# as3320-Bandpass.net
KiCad netlist of a schematic drawn in EAGLE
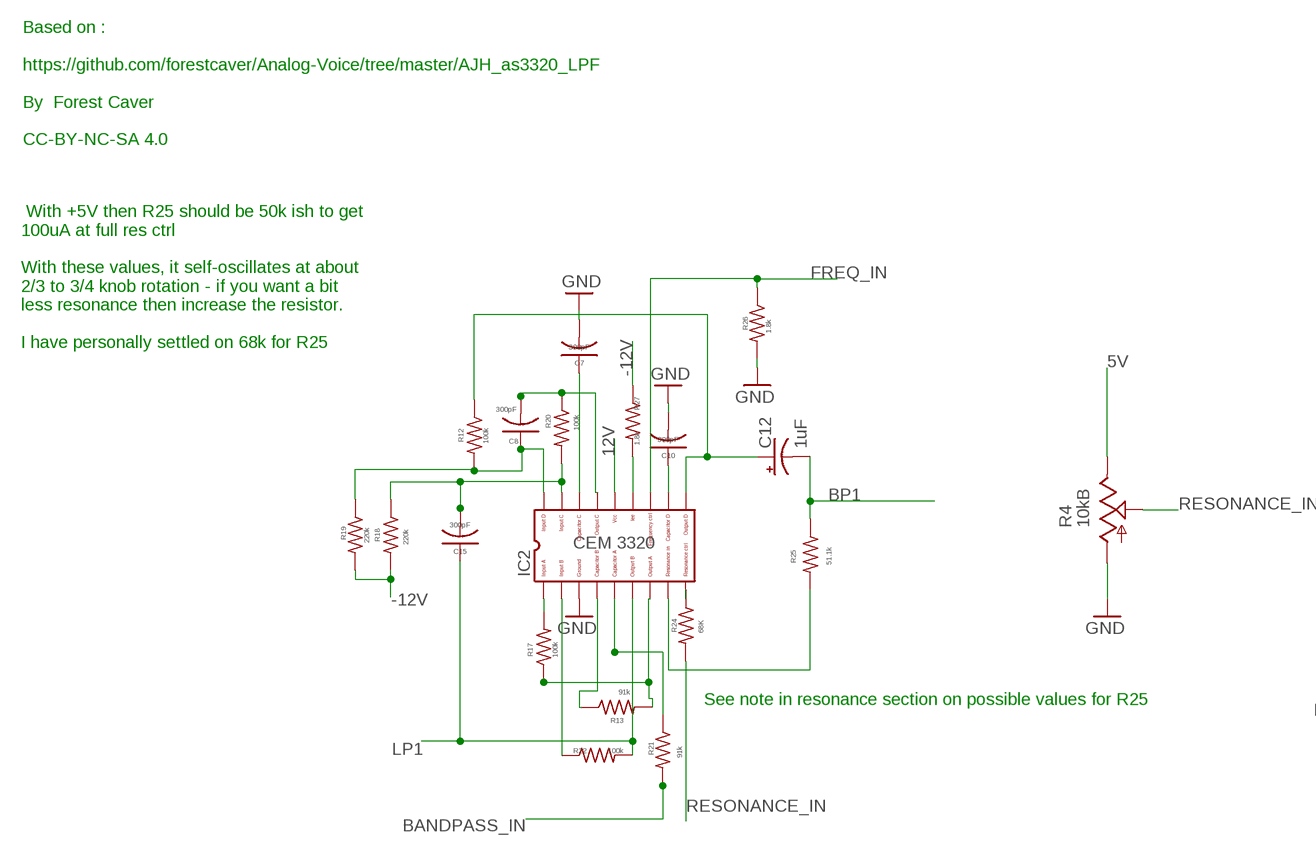
[diagram p0: schematic, sheet 1, part 1 of 2]
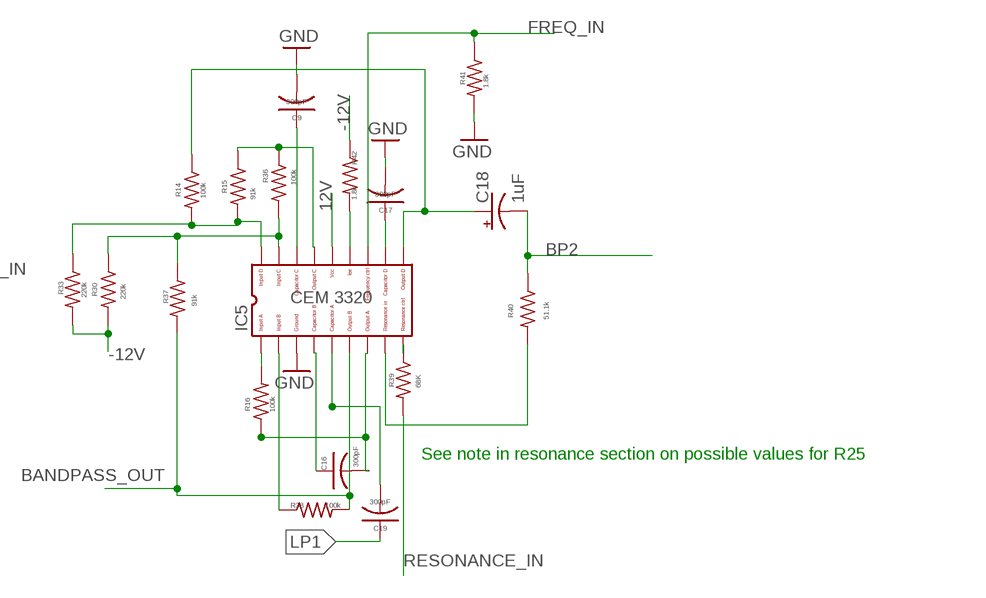
[diagram p1: schematic, sheet 1, part 2 of 2]
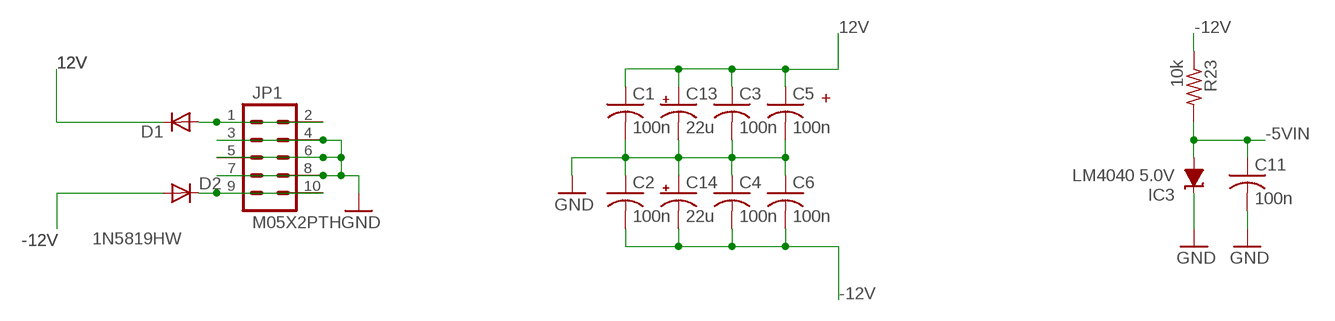
[diagram p2: schematic, sheet 2]
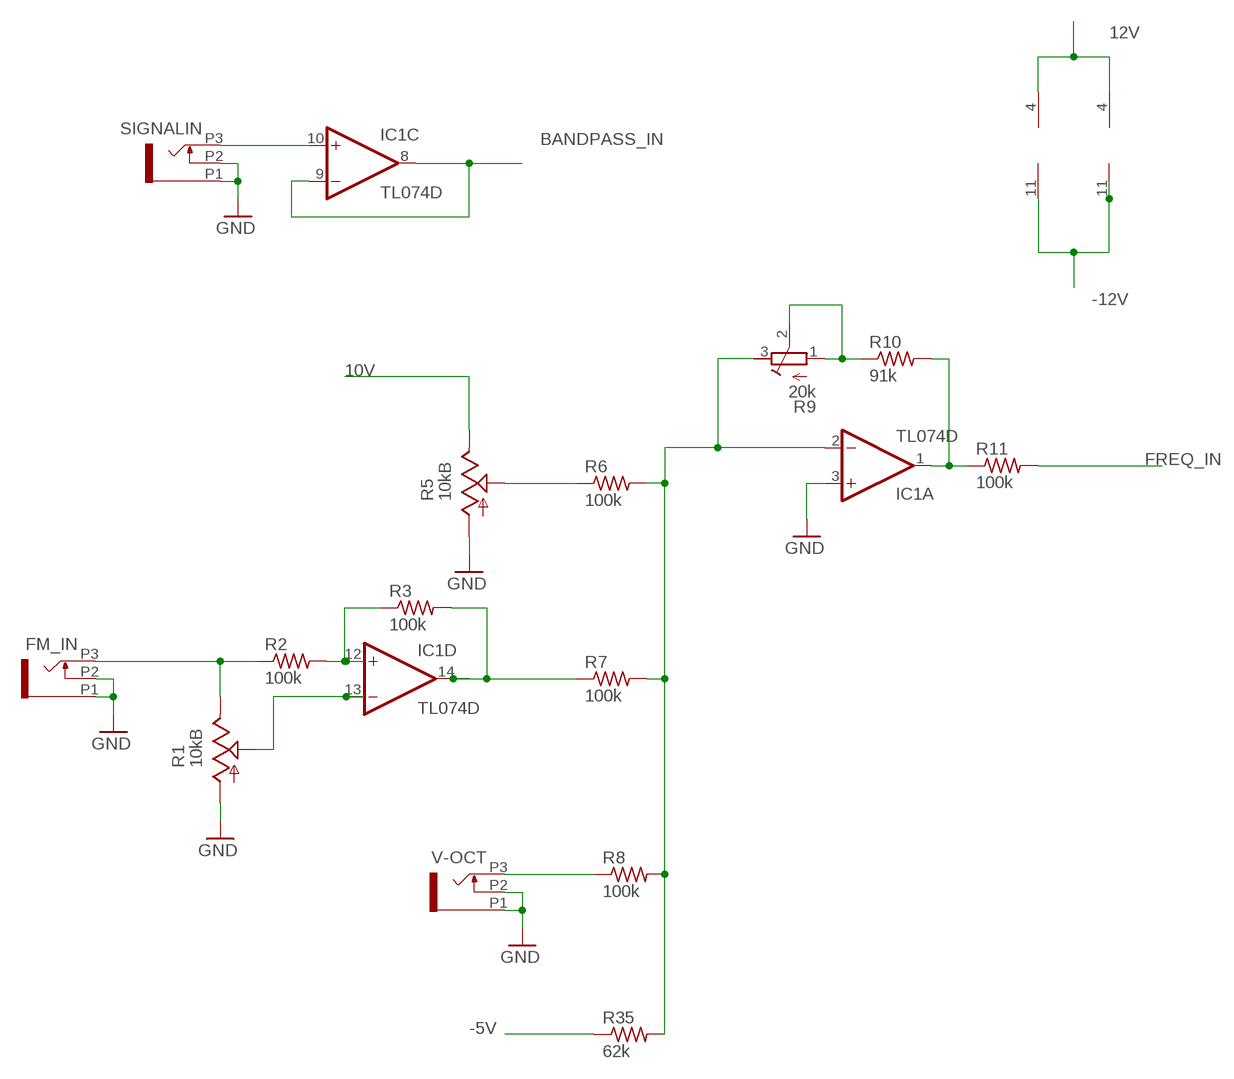
[diagram p3: schematic, sheet 3]
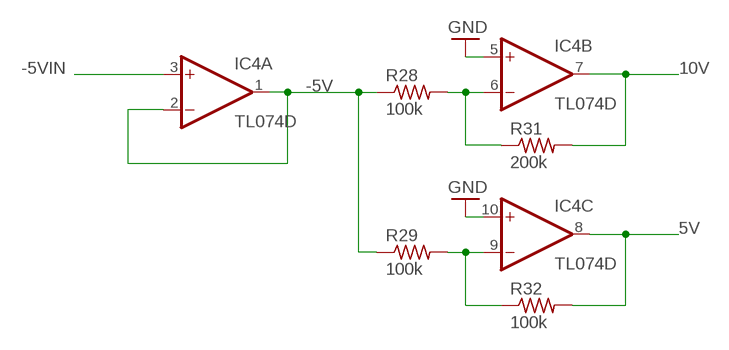
[diagram p4: schematic, sheet 4]
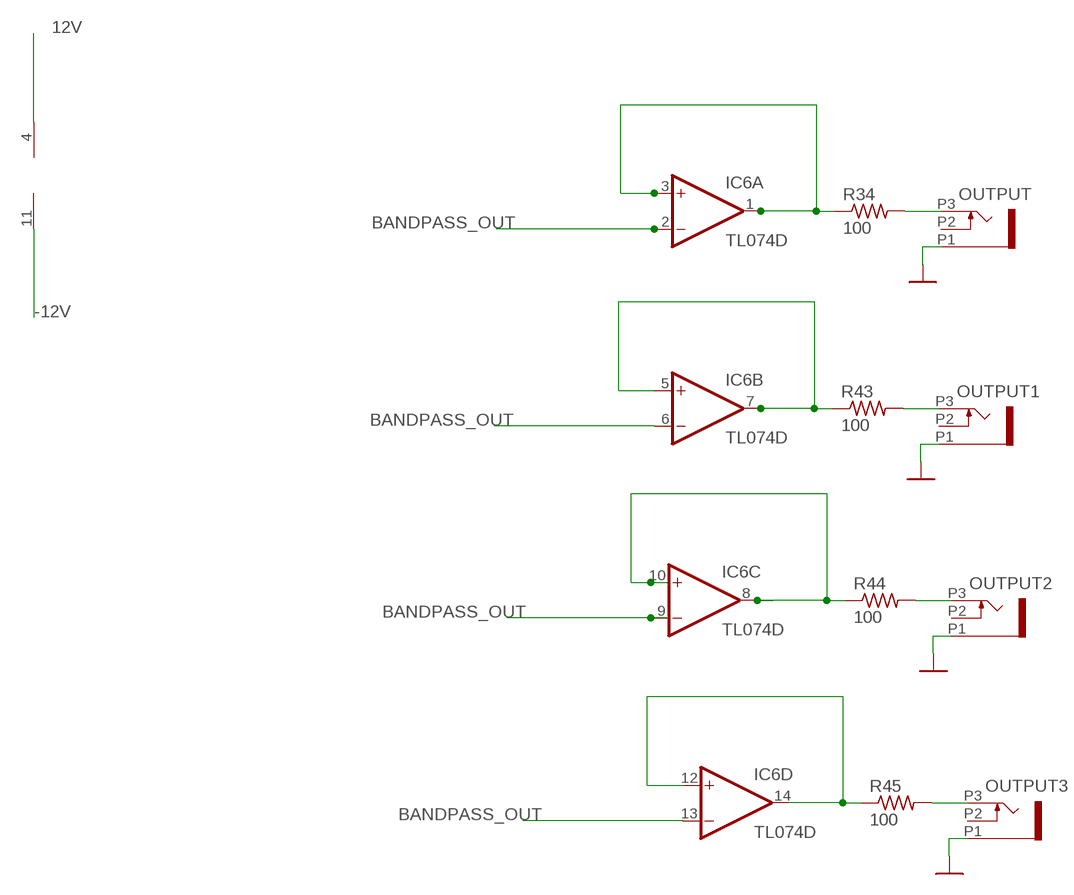
[diagram p5: schematic, sheet 6]

(export (version "E")
  (design (tool "Eeschema 10.0.6"))
  (components
    (comp (ref "C7")
      (value "300pF")
      (footprint "eagle-import:C0603")
      (libsource (lib "eagle-import") (part "rcl_334_C-USC0603"))
    )
    (comp (ref "C8")
      (value "300pF")
      (footprint "eagle-import:C0603")
      (libsource (lib "eagle-import") (part "rcl_334_C-USC0603"))
    )
    (comp (ref "C9")
      (value "300pF")
      (footprint "eagle-import:C0603")
      (libsource (lib "eagle-import") (part "rcl_334_C-USC0603"))
    )
    (comp (ref "C10")
      (value "300pF")
      (footprint "eagle-import:C0603")
      (libsource (lib "eagle-import") (part "rcl_334_C-USC0603"))
    )
    (comp (ref "C12")
      (value "1uF")
      (footprint "eagle-import:PANASONIC_B")
      (libsource (lib "eagle-import") (part "rcl_334_CPOL-USB"))
    )
    (comp (ref "C15")
      (value "300pF")
      (footprint "eagle-import:C0603")
      (libsource (lib "eagle-import") (part "rcl_334_C-USC0603"))
    )
    (comp (ref "C16")
      (value "300pF")
      (footprint "eagle-import:C0603")
      (libsource (lib "eagle-import") (part "rcl_334_C-USC0603"))
    )
    (comp (ref "C17")
      (value "300pF")
      (footprint "eagle-import:C0603")
      (libsource (lib "eagle-import") (part "rcl_334_C-USC0603"))
    )
    (comp (ref "C18")
      (value "1uF")
      (footprint "eagle-import:PANASONIC_B")
      (libsource (lib "eagle-import") (part "rcl_334_CPOL-USB"))
    )
    (comp (ref "C19")
      (value "300pF")
      (footprint "eagle-import:C0603")
      (libsource (lib "eagle-import") (part "rcl_334_C-USC0603"))
    )
    (comp (ref "IC2")
      (value "CEM3320")
      (footprint "eagle-import:DIL18")
      (libsource (lib "eagle-import") (part "CEM3320"))
    )
    (comp (ref "IC5")
      (value "CEM3320")
      (footprint "eagle-import:DIL18")
      (libsource (lib "eagle-import") (part "CEM3320"))
    )
    (comp (ref "R4")
      (value "10kB")
      (footprint "eagle-import:ALPS_POT_VERTICAL")
      (libsource (lib "eagle-import") (part "POT_USVERTICAL"))
    )
    (comp (ref "R12")
      (value "100k")
      (footprint "eagle-import:R0603")
      (libsource (lib "eagle-import") (part "R-US_R0603"))
    )
    (comp (ref "R13")
      (value "91k")
      (footprint "eagle-import:R0603")
      (libsource (lib "eagle-import") (part "R-US_R0603"))
    )
    (comp (ref "R14")
      (value "100k")
      (footprint "eagle-import:R0603")
      (libsource (lib "eagle-import") (part "R-US_R0603"))
    )
    (comp (ref "R15")
      (value "91k")
      (footprint "eagle-import:R0603")
      (libsource (lib "eagle-import") (part "R-US_R0603"))
    )
    (comp (ref "R16")
      (value "100k")
      (footprint "eagle-import:R0603")
      (libsource (lib "eagle-import") (part "R-US_R0603"))
    )
    (comp (ref "R17")
      (value "100k")
      (footprint "eagle-import:R0603")
      (libsource (lib "eagle-import") (part "R-US_R0603"))
    )
    (comp (ref "R18")
      (value "220k")
      (footprint "eagle-import:R0603")
      (libsource (lib "eagle-import") (part "R-US_R0603"))
    )
    (comp (ref "R19")
      (value "220k")
      (footprint "eagle-import:R0603")
      (libsource (lib "eagle-import") (part "R-US_R0603"))
    )
    (comp (ref "R20")
      (value "100k")
      (footprint "eagle-import:R0603")
      (libsource (lib "eagle-import") (part "R-US_R0603"))
    )
    (comp (ref "R21")
      (value "91k")
      (footprint "eagle-import:R0603")
      (libsource (lib "eagle-import") (part "R-US_R0603"))
    )
    (comp (ref "R22")
      (value "100k")
      (footprint "eagle-import:R0603")
      (libsource (lib "eagle-import") (part "R-US_R0603"))
    )
    (comp (ref "R24")
      (value "68K")
      (footprint "eagle-import:R0603")
      (libsource (lib "eagle-import") (part "R-US_R0603"))
    )
    (comp (ref "R25")
      (value "51.1k")
      (footprint "eagle-import:R0603")
      (libsource (lib "eagle-import") (part "R-US_R0603"))
    )
    (comp (ref "R26")
      (value "1.8k")
      (footprint "eagle-import:R0603")
      (libsource (lib "eagle-import") (part "R-US_R0603"))
    )
    (comp (ref "R27")
      (value "1.8k")
      (footprint "eagle-import:R0603")
      (libsource (lib "eagle-import") (part "R-US_R0603"))
    )
    (comp (ref "R30")
      (value "220k")
      (footprint "eagle-import:R0603")
      (libsource (lib "eagle-import") (part "R-US_R0603"))
    )
    (comp (ref "R33")
      (value "220k")
      (footprint "eagle-import:R0603")
      (libsource (lib "eagle-import") (part "R-US_R0603"))
    )
    (comp (ref "R36")
      (value "100k")
      (footprint "eagle-import:R0603")
      (libsource (lib "eagle-import") (part "R-US_R0603"))
    )
    (comp (ref "R37")
      (value "91k")
      (footprint "eagle-import:R0603")
      (libsource (lib "eagle-import") (part "R-US_R0603"))
    )
    (comp (ref "R38")
      (value "100k")
      (footprint "eagle-import:R0603")
      (libsource (lib "eagle-import") (part "R-US_R0603"))
    )
    (comp (ref "R39")
      (value "68K")
      (footprint "eagle-import:R0603")
      (libsource (lib "eagle-import") (part "R-US_R0603"))
    )
    (comp (ref "R40")
      (value "51.1k")
      (footprint "eagle-import:R0603")
      (libsource (lib "eagle-import") (part "R-US_R0603"))
    )
    (comp (ref "R41")
      (value "1.8k")
      (footprint "eagle-import:R0603")
      (libsource (lib "eagle-import") (part "R-US_R0603"))
    )
    (comp (ref "R42")
      (value "1.8k")
      (footprint "eagle-import:R0603")
      (libsource (lib "eagle-import") (part "R-US_R0603"))
    )
    (comp (ref "FM_IN")
      (value "PJ301_THONKICONN6")
      (footprint "eagle-import:WQP_PJ_301M6")
      (libsource (lib "eagle-import") (part "PJ301_THONKICONN6"))
    )
    (comp (ref "IC1")
      (value "TL074D")
      (footprint "eagle-import:SO14")
      (libsource (lib "eagle-import") (part "TL074D"))
    )
    (comp (ref "IC4")
      (value "TL074D")
      (footprint "eagle-import:SO14")
      (libsource (lib "eagle-import") (part "TL074D"))
    )
    (comp (ref "R1")
      (value "10kB")
      (footprint "eagle-import:ALPS_POT_VERTICAL")
      (libsource (lib "eagle-import") (part "POT_USVERTICAL"))
    )
    (comp (ref "R2")
      (value "100k")
      (footprint "eagle-import:R0603")
      (libsource (lib "eagle-import") (part "resistor_R-US_R0603"))
    )
    (comp (ref "R3")
      (value "100k")
      (footprint "eagle-import:R0603")
      (libsource (lib "eagle-import") (part "resistor_R-US_R0603"))
    )
    (comp (ref "R5")
      (value "10kB")
      (footprint "eagle-import:ALPS_POT_VERTICAL")
      (libsource (lib "eagle-import") (part "POT_USVERTICAL"))
    )
    (comp (ref "R6")
      (value "100k")
      (footprint "eagle-import:R0603")
      (libsource (lib "eagle-import") (part "resistor_R-US_R0603"))
    )
    (comp (ref "R7")
      (value "100k")
      (footprint "eagle-import:R0603")
      (libsource (lib "eagle-import") (part "resistor_R-US_R0603"))
    )
    (comp (ref "R8")
      (value "100k")
      (footprint "eagle-import:R0603")
      (libsource (lib "eagle-import") (part "resistor_R-US_R0603"))
    )
    (comp (ref "R9")
      (value "20k")
      (footprint "eagle-import:RTRIM3296X")
      (libsource (lib "eagle-import") (part "R-TRIMM3296X"))
    )
    (comp (ref "R10")
      (value "91k")
      (footprint "eagle-import:R0603")
      (libsource (lib "eagle-import") (part "resistor_R-US_R0603"))
    )
    (comp (ref "R11")
      (value "100k")
      (footprint "eagle-import:R0603")
      (libsource (lib "eagle-import") (part "resistor_R-US_R0603"))
    )
    (comp (ref "R35")
      (value "62k")
      (footprint "eagle-import:R0603")
      (libsource (lib "eagle-import") (part "resistor_R-US_R0603"))
    )
    (comp (ref "SIGNALIN")
      (value "PJ301_THONKICONN6")
      (footprint "eagle-import:WQP_PJ_301M6")
      (libsource (lib "eagle-import") (part "PJ301_THONKICONN6"))
    )
    (comp (ref "V-OCT")
      (value "PJ301_THONKICONN6")
      (footprint "eagle-import:WQP_PJ_301M6")
      (libsource (lib "eagle-import") (part "PJ301_THONKICONN6"))
    )
    (comp (ref "C1")
      (value "100n")
      (footprint "eagle-import:C0603")
      (libsource (lib "eagle-import") (part "C-USC0603"))
    )
    (comp (ref "C2")
      (value "100n")
      (footprint "eagle-import:C0603")
      (libsource (lib "eagle-import") (part "C-USC0603"))
    )
    (comp (ref "C3")
      (value "100n")
      (footprint "eagle-import:C0603")
      (libsource (lib "eagle-import") (part "C-USC0603"))
    )
    (comp (ref "C4")
      (value "100n")
      (footprint "eagle-import:C0603")
      (libsource (lib "eagle-import") (part "C-USC0603"))
    )
    (comp (ref "C5")
      (value "100n")
      (footprint "eagle-import:C0603")
      (libsource (lib "eagle-import") (part "C-USC0603"))
    )
    (comp (ref "C6")
      (value "100n")
      (footprint "eagle-import:C0603")
      (libsource (lib "eagle-import") (part "C-USC0603"))
    )
    (comp (ref "C11")
      (value "100n")
      (footprint "eagle-import:C0603")
      (libsource (lib "eagle-import") (part "C-USC0603"))
    )
    (comp (ref "C13")
      (value "22u")
      (footprint "eagle-import:PANASONIC_B")
      (libsource (lib "eagle-import") (part "CPOL-USB"))
    )
    (comp (ref "C14")
      (value "22u")
      (footprint "eagle-import:PANASONIC_B")
      (libsource (lib "eagle-import") (part "CPOL-USB"))
    )
    (comp (ref "D1")
      (value "1N5819HW")
      (footprint "eagle-import:SOD123")
      (libsource (lib "eagle-import") (part "DIODE-SOD123"))
    )
    (comp (ref "D2")
      (value "1N5819HW")
      (footprint "eagle-import:SOD123")
      (libsource (lib "eagle-import") (part "DIODE-SOD123"))
    )
    (comp (ref "IC3")
      (value "LM4040 5.0V")
      (footprint "eagle-import:DBZ_R-PDSO-G3")
      (libsource (lib "eagle-import") (part "LM4041DBZC12"))
    )
    (comp (ref "JP1")
      (value "M05X2PTH")
      (footprint "eagle-import:AVR_ICSP")
      (libsource (lib "eagle-import") (part "M05X2PTH"))
    )
    (comp (ref "R23")
      (value "10k")
      (footprint "eagle-import:R0603")
      (libsource (lib "eagle-import") (part "resistor_R-US_R0603"))
    )
    (comp (ref "R28")
      (value "100k")
      (footprint "eagle-import:R0603")
      (libsource (lib "eagle-import") (part "resistor_R-US_R0603"))
    )
    (comp (ref "R29")
      (value "100k")
      (footprint "eagle-import:R0603")
      (libsource (lib "eagle-import") (part "resistor_R-US_R0603"))
    )
    (comp (ref "R31")
      (value "200k")
      (footprint "eagle-import:R0603")
      (libsource (lib "eagle-import") (part "resistor_R-US_R0603"))
    )
    (comp (ref "R32")
      (value "100k")
      (footprint "eagle-import:R0603")
      (libsource (lib "eagle-import") (part "resistor_R-US_R0603"))
    )
    (comp (ref "IC6")
      (value "TL074D")
      (footprint "eagle-import:SO14")
      (libsource (lib "eagle-import") (part "TL074D"))
    )
    (comp (ref "OUTPUT")
      (value "PJ301_THONKICONN6")
      (footprint "eagle-import:WQP_PJ_301M6")
      (libsource (lib "eagle-import") (part "PJ301_THONKICONN6"))
    )
    (comp (ref "OUTPUT1")
      (value "PJ301_THONKICONN6")
      (footprint "eagle-import:WQP_PJ_301M6")
      (libsource (lib "eagle-import") (part "PJ301_THONKICONN6"))
    )
    (comp (ref "OUTPUT2")
      (value "PJ301_THONKICONN6")
      (footprint "eagle-import:WQP_PJ_301M6")
      (libsource (lib "eagle-import") (part "PJ301_THONKICONN6"))
    )
    (comp (ref "OUTPUT3")
      (value "PJ301_THONKICONN6")
      (footprint "eagle-import:WQP_PJ_301M6")
      (libsource (lib "eagle-import") (part "PJ301_THONKICONN6"))
    )
    (comp (ref "R34")
      (value "100")
      (footprint "eagle-import:R0603")
      (libsource (lib "eagle-import") (part "resistor_R-US_R0603"))
    )
    (comp (ref "R43")
      (value "100")
      (footprint "eagle-import:R0603")
      (libsource (lib "eagle-import") (part "resistor_R-US_R0603"))
    )
    (comp (ref "R44")
      (value "100")
      (footprint "eagle-import:R0603")
      (libsource (lib "eagle-import") (part "resistor_R-US_R0603"))
    )
    (comp (ref "R45")
      (value "100")
      (footprint "eagle-import:R0603")
      (libsource (lib "eagle-import") (part "resistor_R-US_R0603"))
    )
  )
  (nets
    (net (code "1") (name "-5V") (class "Default")
      (node (ref "IC4") (pin "1") (pinfunction "OUT_1") (pintype "output"))
      (node (ref "IC4") (pin "2") (pinfunction "-IN_2") (pintype "input"))
      (node (ref "R28") (pin "1") (pinfunction "1_1") (pintype "passive"))
      (node (ref "R29") (pin "1") (pinfunction "1_1") (pintype "passive"))
      (node (ref "R35") (pin "1") (pinfunction "1_1") (pintype "passive"))
    )
    (net (code "2") (name "-5VIN") (class "Default")
      (node (ref "C11") (pin "1") (pinfunction "1_1") (pintype "passive"))
      (node (ref "IC3") (pin "2") (pinfunction "A_2") (pintype "passive"))
      (node (ref "IC4") (pin "3") (pinfunction "+IN_3") (pintype "input"))
      (node (ref "R23") (pin "2") (pinfunction "2_2") (pintype "passive"))
    )
    (net (code "3") (name "-12V") (class "Default")
      (node (ref "C14") (pin "-") (pinfunction "-_-") (pintype "passive"))
      (node (ref "C2") (pin "2") (pinfunction "2_2") (pintype "passive"))
      (node (ref "C4") (pin "2") (pinfunction "2_2") (pintype "passive"))
      (node (ref "C6") (pin "2") (pinfunction "2_2") (pintype "passive"))
      (node (ref "D2") (pin "A") (pinfunction "A_A") (pintype "passive"))
      (node (ref "IC1") (pin "11") (pinfunction "V-_11") (pintype "power_in"))
      (node (ref "IC4") (pin "11") (pinfunction "V-_11") (pintype "power_in"))
      (node (ref "IC6") (pin "11") (pinfunction "V-_11") (pintype "power_in"))
      (node (ref "R18") (pin "2") (pinfunction "2_2") (pintype "passive"))
      (node (ref "R19") (pin "2") (pinfunction "2_2") (pintype "passive"))
      (node (ref "R23") (pin "1") (pinfunction "1_1") (pintype "passive"))
      (node (ref "R27") (pin "1") (pinfunction "1_1") (pintype "passive"))
      (node (ref "R30") (pin "2") (pinfunction "2_2") (pintype "passive"))
      (node (ref "R33") (pin "2") (pinfunction "2_2") (pintype "passive"))
      (node (ref "R42") (pin "1") (pinfunction "1_1") (pintype "passive"))
    )
    (net (code "4") (name "5V") (class "Default")
      (node (ref "IC4") (pin "8") (pinfunction "OUT_8") (pintype "output"))
      (node (ref "R32") (pin "2") (pinfunction "2_2") (pintype "passive"))
      (node (ref "R4") (pin "P$1") (pinfunction "E_P$1") (pintype "passive"))
    )
    (net (code "5") (name "10V") (class "Default")
      (node (ref "IC4") (pin "7") (pinfunction "OUT_7") (pintype "output"))
      (node (ref "R31") (pin "2") (pinfunction "2_2") (pintype "passive"))
      (node (ref "R5") (pin "P$1") (pinfunction "E_P$1") (pintype "passive"))
    )
    (net (code "6") (name "12V") (class "Default")
      (node (ref "C1") (pin "1") (pinfunction "1_1") (pintype "passive"))
      (node (ref "C13") (pin "+") (pinfunction "+_+") (pintype "passive"))
      (node (ref "C3") (pin "1") (pinfunction "1_1") (pintype "passive"))
      (node (ref "C5") (pin "1") (pinfunction "1_1") (pintype "passive"))
      (node (ref "D1") (pin "C") (pinfunction "C_C") (pintype "passive"))
      (node (ref "IC1") (pin "4") (pinfunction "V+_4") (pintype "power_in"))
      (node (ref "IC2") (pin "14") (pinfunction "14_14") (pintype "power_in"))
      (node (ref "IC4") (pin "4") (pinfunction "V+_4") (pintype "power_in"))
      (node (ref "IC5") (pin "14") (pinfunction "14_14") (pintype "power_in"))
      (node (ref "IC6") (pin "4") (pinfunction "V+_4") (pintype "power_in"))
    )
    (net (code "7") (name "BANDPASS_IN") (class "Default")
      (node (ref "IC1") (pin "8") (pinfunction "OUT_8") (pintype "output"))
      (node (ref "IC1") (pin "9") (pinfunction "-IN_9") (pintype "input"))
      (node (ref "R21") (pin "2") (pinfunction "2_2") (pintype "passive"))
    )
    (net (code "8") (name "BANDPASS_OUT") (class "Default")
      (node (ref "IC5") (pin "6") (pinfunction "6_6") (pintype "output"))
      (node (ref "IC6") (pin "13") (pinfunction "-IN_13") (pintype "input"))
      (node (ref "IC6") (pin "2") (pinfunction "-IN_2") (pintype "input"))
      (node (ref "IC6") (pin "6") (pinfunction "-IN_6") (pintype "input"))
      (node (ref "IC6") (pin "9") (pinfunction "-IN_9") (pintype "input"))
      (node (ref "R37") (pin "2") (pinfunction "2_2") (pintype "passive"))
      (node (ref "R38") (pin "2") (pinfunction "2_2") (pintype "passive"))
    )
    (net (code "9") (name "BP1") (class "Default")
      (node (ref "C12") (pin "-") (pinfunction "-_-") (pintype "passive"))
      (node (ref "R25") (pin "1") (pinfunction "1_1") (pintype "passive"))
    )
    (net (code "10") (name "BP2") (class "Default")
      (node (ref "C18") (pin "-") (pinfunction "-_-") (pintype "passive"))
      (node (ref "R40") (pin "1") (pinfunction "1_1") (pintype "passive"))
    )
    (net (code "11") (name "FREQ_IN") (class "Default")
      (node (ref "IC2") (pin "12") (pinfunction "12_12") (pintype "bidirectional"))
      (node (ref "IC5") (pin "12") (pinfunction "12_12") (pintype "bidirectional"))
      (node (ref "R11") (pin "2") (pinfunction "2_2") (pintype "passive"))
      (node (ref "R26") (pin "1") (pinfunction "1_1") (pintype "passive"))
      (node (ref "R41") (pin "1") (pinfunction "1_1") (pintype "passive"))
    )
    (net (code "12") (name "GND") (class "Default")
      (node (ref "C1") (pin "2") (pinfunction "2_2") (pintype "passive"))
      (node (ref "C10") (pin "2") (pinfunction "2_2") (pintype "passive"))
      (node (ref "C11") (pin "2") (pinfunction "2_2") (pintype "passive"))
      (node (ref "C13") (pin "-") (pinfunction "-_-") (pintype "passive"))
      (node (ref "C14") (pin "+") (pinfunction "+_+") (pintype "passive"))
      (node (ref "C17") (pin "2") (pinfunction "2_2") (pintype "passive"))
      (node (ref "C2") (pin "1") (pinfunction "1_1") (pintype "passive"))
      (node (ref "C3") (pin "2") (pinfunction "2_2") (pintype "passive"))
      (node (ref "C4") (pin "1") (pinfunction "1_1") (pintype "passive"))
      (node (ref "C5") (pin "2") (pinfunction "2_2") (pintype "passive"))
      (node (ref "C6") (pin "1") (pinfunction "1_1") (pintype "passive"))
      (node (ref "C7") (pin "2") (pinfunction "2_2") (pintype "passive"))
      (node (ref "C9") (pin "2") (pinfunction "2_2") (pintype "passive"))
      (node (ref "FM_IN") (pin "P1") (pinfunction "1_P1") (pintype "passive"))
      (node (ref "FM_IN") (pin "P2") (pinfunction "2_P2") (pintype "passive"))
      (node (ref "IC1") (pin "3") (pinfunction "+IN_3") (pintype "input"))
      (node (ref "IC2") (pin "3") (pinfunction "3_3") (pintype "power_in"))
      (node (ref "IC3") (pin "1") (pinfunction "C_1") (pintype "passive"))
      (node (ref "IC4") (pin "10") (pinfunction "+IN_10") (pintype "input"))
      (node (ref "IC4") (pin "5") (pinfunction "+IN_5") (pintype "input"))
      (node (ref "IC5") (pin "3") (pinfunction "3_3") (pintype "power_in"))
      (node (ref "JP1") (pin "3") (pinfunction "3_3") (pintype "passive"))
      (node (ref "JP1") (pin "4") (pinfunction "4_4") (pintype "passive"))
      (node (ref "JP1") (pin "5") (pinfunction "5_5") (pintype "passive"))
      (node (ref "JP1") (pin "6") (pinfunction "6_6") (pintype "passive"))
      (node (ref "JP1") (pin "7") (pinfunction "7_7") (pintype "passive"))
      (node (ref "JP1") (pin "8") (pinfunction "8_8") (pintype "passive"))
      (node (ref "OUTPUT") (pin "P1") (pinfunction "1_P1") (pintype "passive"))
      (node (ref "OUTPUT1") (pin "P1") (pinfunction "1_P1") (pintype "passive"))
      (node (ref "OUTPUT2") (pin "P1") (pinfunction "1_P1") (pintype "passive"))
      (node (ref "OUTPUT3") (pin "P1") (pinfunction "1_P1") (pintype "passive"))
      (node (ref "R1") (pin "P$3") (pinfunction "A_P$3") (pintype "passive"))
      (node (ref "R26") (pin "2") (pinfunction "2_2") (pintype "passive"))
      (node (ref "R4") (pin "P$3") (pinfunction "A_P$3") (pintype "passive"))
      (node (ref "R41") (pin "2") (pinfunction "2_2") (pintype "passive"))
      (node (ref "R5") (pin "P$3") (pinfunction "A_P$3") (pintype "passive"))
      (node (ref "SIGNALIN") (pin "P1") (pinfunction "1_P1") (pintype "passive"))
      (node (ref "SIGNALIN") (pin "P2") (pinfunction "2_P2") (pintype "passive"))
      (node (ref "V-OCT") (pin "P1") (pinfunction "1_P1") (pintype "passive"))
      (node (ref "V-OCT") (pin "P2") (pinfunction "2_P2") (pintype "passive"))
    )
    (net (code "13") (name "LP1") (class "Default")
      (node (ref "C15") (pin "1") (pinfunction "1_1") (pintype "passive"))
      (node (ref "C19") (pin "1") (pinfunction "1_1") (pintype "passive"))
      (node (ref "IC2") (pin "6") (pinfunction "6_6") (pintype "output"))
      (node (ref "R22") (pin "2") (pinfunction "2_2") (pintype "passive"))
    )
    (net (code "14") (name "Net-(C7-Pad1)") (class "Default")
      (node (ref "C7") (pin "1") (pinfunction "1_1") (pintype "passive"))
      (node (ref "IC2") (pin "16") (pinfunction "16_16") (pintype "bidirectional"))
    )
    (net (code "15") (name "Net-(C8-Pad1)") (class "Default")
      (node (ref "C8") (pin "1") (pinfunction "1_1") (pintype "passive"))
      (node (ref "IC2") (pin "18") (pinfunction "18_18") (pintype "input"))
      (node (ref "R12") (pin "2") (pinfunction "2_2") (pintype "passive"))
      (node (ref "R19") (pin "1") (pinfunction "1_1") (pintype "passive"))
    )
    (net (code "16") (name "Net-(C8-Pad2)") (class "Default")
      (node (ref "C8") (pin "2") (pinfunction "2_2") (pintype "passive"))
      (node (ref "IC2") (pin "15") (pinfunction "15_15") (pintype "output"))
      (node (ref "R20") (pin "1") (pinfunction "1_1") (pintype "passive"))
    )
    (net (code "17") (name "Net-(C9-Pad1)") (class "Default")
      (node (ref "C9") (pin "1") (pinfunction "1_1") (pintype "passive"))
      (node (ref "IC5") (pin "16") (pinfunction "16_16") (pintype "bidirectional"))
    )
    (net (code "18") (name "Net-(C10-Pad1)") (class "Default")
      (node (ref "C10") (pin "1") (pinfunction "1_1") (pintype "passive"))
      (node (ref "IC2") (pin "11") (pinfunction "11_11") (pintype "output"))
    )
    (net (code "19") (name "Net-(C12-Pad+)") (class "Default")
      (node (ref "C12") (pin "+") (pinfunction "+_+") (pintype "passive"))
      (node (ref "IC2") (pin "10") (pinfunction "10_10") (pintype "output"))
      (node (ref "R12") (pin "1") (pinfunction "1_1") (pintype "passive"))
    )
    (net (code "20") (name "Net-(C15-Pad2)") (class "Default")
      (node (ref "C15") (pin "2") (pinfunction "2_2") (pintype "passive"))
      (node (ref "IC2") (pin "17") (pinfunction "17_17") (pintype "input"))
      (node (ref "R18") (pin "1") (pinfunction "1_1") (pintype "passive"))
      (node (ref "R20") (pin "2") (pinfunction "2_2") (pintype "passive"))
    )
    (net (code "21") (name "Net-(C16-Pad1)") (class "Default")
      (node (ref "C16") (pin "1") (pinfunction "1_1") (pintype "passive"))
      (node (ref "IC5") (pin "4") (pinfunction "4_4") (pintype "bidirectional"))
    )
    (net (code "22") (name "Net-(C16-Pad2)") (class "Default")
      (node (ref "C16") (pin "2") (pinfunction "2_2") (pintype "passive"))
      (node (ref "IC5") (pin "7") (pinfunction "7_7") (pintype "output"))
      (node (ref "R16") (pin "1") (pinfunction "1_1") (pintype "passive"))
    )
    (net (code "23") (name "Net-(C17-Pad1)") (class "Default")
      (node (ref "C17") (pin "1") (pinfunction "1_1") (pintype "passive"))
      (node (ref "IC5") (pin "11") (pinfunction "11_11") (pintype "output"))
    )
    (net (code "24") (name "Net-(C18-Pad+)") (class "Default")
      (node (ref "C18") (pin "+") (pinfunction "+_+") (pintype "passive"))
      (node (ref "IC5") (pin "10") (pinfunction "10_10") (pintype "output"))
      (node (ref "R14") (pin "1") (pinfunction "1_1") (pintype "passive"))
    )
    (net (code "25") (name "Net-(C19-Pad2)") (class "Default")
      (node (ref "C19") (pin "2") (pinfunction "2_2") (pintype "passive"))
      (node (ref "IC5") (pin "5") (pinfunction "5_5") (pintype "bidirectional"))
    )
    (net (code "26") (name "Net-(D1-PadA)") (class "Default")
      (node (ref "D1") (pin "A") (pinfunction "A_A") (pintype "passive"))
      (node (ref "JP1") (pin "1") (pinfunction "1_1") (pintype "passive"))
      (node (ref "JP1") (pin "2") (pinfunction "2_2") (pintype "passive"))
    )
    (net (code "27") (name "Net-(D2-PadC)") (class "Default")
      (node (ref "D2") (pin "C") (pinfunction "C_C") (pintype "passive"))
      (node (ref "JP1") (pin "10") (pinfunction "10_10") (pintype "passive"))
      (node (ref "JP1") (pin "9") (pinfunction "9_9") (pintype "passive"))
    )
    (net (code "28") (name "Net-(FM_IN-3)") (class "Default")
      (node (ref "FM_IN") (pin "P3") (pinfunction "3_P3") (pintype "passive"))
      (node (ref "R1") (pin "P$1") (pinfunction "E_P$1") (pintype "passive"))
      (node (ref "R2") (pin "1") (pinfunction "1_1") (pintype "passive"))
    )
    (net (code "29") (name "Net-(IC1A--IN)") (class "Default")
      (node (ref "IC1") (pin "2") (pinfunction "-IN_2") (pintype "input"))
      (node (ref "R35") (pin "2") (pinfunction "2_2") (pintype "passive"))
      (node (ref "R6") (pin "2") (pinfunction "2_2") (pintype "passive"))
      (node (ref "R7") (pin "2") (pinfunction "2_2") (pintype "passive"))
      (node (ref "R8") (pin "2") (pinfunction "2_2") (pintype "passive"))
      (node (ref "R9") (pin "3") (pinfunction "A_3") (pintype "passive"))
    )
    (net (code "30") (name "Net-(IC1A-OUT)") (class "Default")
      (node (ref "IC1") (pin "1") (pinfunction "OUT_1") (pintype "output"))
      (node (ref "R10") (pin "2") (pinfunction "2_2") (pintype "passive"))
      (node (ref "R11") (pin "1") (pinfunction "1_1") (pintype "passive"))
    )
    (net (code "31") (name "Net-(IC1C-+IN)") (class "Default")
      (node (ref "IC1") (pin "10") (pinfunction "+IN_10") (pintype "input"))
      (node (ref "SIGNALIN") (pin "P3") (pinfunction "3_P3") (pintype "passive"))
    )
    (net (code "32") (name "Net-(IC1D-+IN)") (class "Default")
      (node (ref "IC1") (pin "12") (pinfunction "+IN_12") (pintype "input"))
      (node (ref "R2") (pin "2") (pinfunction "2_2") (pintype "passive"))
      (node (ref "R3") (pin "1") (pinfunction "1_1") (pintype "passive"))
    )
    (net (code "33") (name "Net-(IC1D--IN)") (class "Default")
      (node (ref "IC1") (pin "13") (pinfunction "-IN_13") (pintype "input"))
      (node (ref "R1") (pin "P$2") (pinfunction "S_P$2") (pintype "passive"))
    )
    (net (code "34") (name "Net-(IC1D-OUT)") (class "Default")
      (node (ref "IC1") (pin "14") (pinfunction "OUT_14") (pintype "output"))
      (node (ref "R3") (pin "2") (pinfunction "2_2") (pintype "passive"))
      (node (ref "R7") (pin "1") (pinfunction "1_1") (pintype "passive"))
    )
    (net (code "35") (name "Net-(IC2-Pad1)") (class "Default")
      (node (ref "IC2") (pin "1") (pinfunction "1_1") (pintype "input"))
      (node (ref "R17") (pin "2") (pinfunction "2_2") (pintype "passive"))
    )
    (net (code "36") (name "Net-(IC2-Pad2)") (class "Default")
      (node (ref "IC2") (pin "2") (pinfunction "2_2") (pintype "input"))
      (node (ref "R22") (pin "1") (pinfunction "1_1") (pintype "passive"))
    )
    (net (code "37") (name "Net-(IC2-Pad4)") (class "Default")
      (node (ref "IC2") (pin "4") (pinfunction "4_4") (pintype "bidirectional"))
      (node (ref "R13") (pin "1") (pinfunction "1_1") (pintype "passive"))
    )
    (net (code "38") (name "Net-(IC2-Pad5)") (class "Default")
      (node (ref "IC2") (pin "5") (pinfunction "5_5") (pintype "bidirectional"))
      (node (ref "R21") (pin "1") (pinfunction "1_1") (pintype "passive"))
    )
    (net (code "39") (name "Net-(IC2-Pad7)") (class "Default")
      (node (ref "IC2") (pin "7") (pinfunction "7_7") (pintype "output"))
      (node (ref "R13") (pin "2") (pinfunction "2_2") (pintype "passive"))
      (node (ref "R17") (pin "1") (pinfunction "1_1") (pintype "passive"))
    )
    (net (code "40") (name "Net-(IC2-Pad8)") (class "Default")
      (node (ref "IC2") (pin "8") (pinfunction "8_8") (pintype "input"))
      (node (ref "R25") (pin "2") (pinfunction "2_2") (pintype "passive"))
    )
    (net (code "41") (name "Net-(IC2-Pad9)") (class "Default")
      (node (ref "IC2") (pin "9") (pinfunction "9_9") (pintype "input"))
      (node (ref "R24") (pin "1") (pinfunction "1_1") (pintype "passive"))
    )
    (net (code "42") (name "Net-(IC2-Pad13)") (class "Default")
      (node (ref "IC2") (pin "13") (pinfunction "13_13") (pintype "power_in"))
      (node (ref "R27") (pin "2") (pinfunction "2_2") (pintype "passive"))
    )
    (net (code "43") (name "Net-(IC4B--IN)") (class "Default")
      (node (ref "IC4") (pin "6") (pinfunction "-IN_6") (pintype "input"))
      (node (ref "R28") (pin "2") (pinfunction "2_2") (pintype "passive"))
      (node (ref "R31") (pin "1") (pinfunction "1_1") (pintype "passive"))
    )
    (net (code "44") (name "Net-(IC4C--IN)") (class "Default")
      (node (ref "IC4") (pin "9") (pinfunction "-IN_9") (pintype "input"))
      (node (ref "R29") (pin "2") (pinfunction "2_2") (pintype "passive"))
      (node (ref "R32") (pin "1") (pinfunction "1_1") (pintype "passive"))
    )
    (net (code "45") (name "Net-(IC5-Pad1)") (class "Default")
      (node (ref "IC5") (pin "1") (pinfunction "1_1") (pintype "input"))
      (node (ref "R16") (pin "2") (pinfunction "2_2") (pintype "passive"))
    )
    (net (code "46") (name "Net-(IC5-Pad2)") (class "Default")
      (node (ref "IC5") (pin "2") (pinfunction "2_2") (pintype "input"))
      (node (ref "R38") (pin "1") (pinfunction "1_1") (pintype "passive"))
    )
    (net (code "47") (name "Net-(IC5-Pad8)") (class "Default")
      (node (ref "IC5") (pin "8") (pinfunction "8_8") (pintype "input"))
      (node (ref "R40") (pin "2") (pinfunction "2_2") (pintype "passive"))
    )
    (net (code "48") (name "Net-(IC5-Pad9)") (class "Default")
      (node (ref "IC5") (pin "9") (pinfunction "9_9") (pintype "input"))
      (node (ref "R39") (pin "1") (pinfunction "1_1") (pintype "passive"))
    )
    (net (code "49") (name "Net-(IC5-Pad13)") (class "Default")
      (node (ref "IC5") (pin "13") (pinfunction "13_13") (pintype "power_in"))
      (node (ref "R42") (pin "2") (pinfunction "2_2") (pintype "passive"))
    )
    (net (code "50") (name "Net-(IC5-Pad15)") (class "Default")
      (node (ref "IC5") (pin "15") (pinfunction "15_15") (pintype "output"))
      (node (ref "R15") (pin "1") (pinfunction "1_1") (pintype "passive"))
      (node (ref "R36") (pin "1") (pinfunction "1_1") (pintype "passive"))
    )
    (net (code "51") (name "Net-(IC5-Pad17)") (class "Default")
      (node (ref "IC5") (pin "17") (pinfunction "17_17") (pintype "input"))
      (node (ref "R30") (pin "1") (pinfunction "1_1") (pintype "passive"))
      (node (ref "R36") (pin "2") (pinfunction "2_2") (pintype "passive"))
      (node (ref "R37") (pin "1") (pinfunction "1_1") (pintype "passive"))
    )
    (net (code "52") (name "Net-(IC5-Pad18)") (class "Default")
      (node (ref "IC5") (pin "18") (pinfunction "18_18") (pintype "input"))
      (node (ref "R14") (pin "2") (pinfunction "2_2") (pintype "passive"))
      (node (ref "R15") (pin "2") (pinfunction "2_2") (pintype "passive"))
      (node (ref "R33") (pin "1") (pinfunction "1_1") (pintype "passive"))
    )
    (net (code "53") (name "Net-(IC6A-+IN)") (class "Default")
      (node (ref "IC6") (pin "1") (pinfunction "OUT_1") (pintype "output"))
      (node (ref "IC6") (pin "3") (pinfunction "+IN_3") (pintype "input"))
      (node (ref "R34") (pin "1") (pinfunction "1_1") (pintype "passive"))
    )
    (net (code "54") (name "Net-(IC6B-+IN)") (class "Default")
      (node (ref "IC6") (pin "5") (pinfunction "+IN_5") (pintype "input"))
      (node (ref "IC6") (pin "7") (pinfunction "OUT_7") (pintype "output"))
      (node (ref "R43") (pin "1") (pinfunction "1_1") (pintype "passive"))
    )
    (net (code "55") (name "Net-(IC6C-+IN)") (class "Default")
      (node (ref "IC6") (pin "10") (pinfunction "+IN_10") (pintype "input"))
      (node (ref "IC6") (pin "8") (pinfunction "OUT_8") (pintype "output"))
      (node (ref "R44") (pin "1") (pinfunction "1_1") (pintype "passive"))
    )
    (net (code "56") (name "Net-(IC6D-+IN)") (class "Default")
      (node (ref "IC6") (pin "12") (pinfunction "+IN_12") (pintype "input"))
      (node (ref "IC6") (pin "14") (pinfunction "OUT_14") (pintype "output"))
      (node (ref "R45") (pin "1") (pinfunction "1_1") (pintype "passive"))
    )
    (net (code "57") (name "Net-(OUTPUT-3)") (class "Default")
      (node (ref "OUTPUT") (pin "P3") (pinfunction "3_P3") (pintype "passive"))
      (node (ref "R34") (pin "2") (pinfunction "2_2") (pintype "passive"))
    )
    (net (code "58") (name "Net-(OUTPUT1-3)") (class "Default")
      (node (ref "OUTPUT1") (pin "P3") (pinfunction "3_P3") (pintype "passive"))
      (node (ref "R43") (pin "2") (pinfunction "2_2") (pintype "passive"))
    )
    (net (code "59") (name "Net-(OUTPUT2-3)") (class "Default")
      (node (ref "OUTPUT2") (pin "P3") (pinfunction "3_P3") (pintype "passive"))
      (node (ref "R44") (pin "2") (pinfunction "2_2") (pintype "passive"))
    )
    (net (code "60") (name "Net-(OUTPUT3-3)") (class "Default")
      (node (ref "OUTPUT3") (pin "P3") (pinfunction "3_P3") (pintype "passive"))
      (node (ref "R45") (pin "2") (pinfunction "2_2") (pintype "passive"))
    )
    (net (code "61") (name "Net-(R5-S)") (class "Default")
      (node (ref "R5") (pin "P$2") (pinfunction "S_P$2") (pintype "passive"))
      (node (ref "R6") (pin "1") (pinfunction "1_1") (pintype "passive"))
    )
    (net (code "62") (name "Net-(R9-E)") (class "Default")
      (node (ref "R10") (pin "1") (pinfunction "1_1") (pintype "passive"))
      (node (ref "R9") (pin "1") (pinfunction "E_1") (pintype "passive"))
      (node (ref "R9") (pin "2") (pinfunction "S_2") (pintype "passive"))
    )
    (net (code "63") (name "Net-(V-OCT-3)") (class "Default")
      (node (ref "R8") (pin "1") (pinfunction "1_1") (pintype "passive"))
      (node (ref "V-OCT") (pin "P3") (pinfunction "3_P3") (pintype "passive"))
    )
    (net (code "64") (name "RESONANCE_IN") (class "Default")
      (node (ref "R24") (pin "2") (pinfunction "2_2") (pintype "passive"))
      (node (ref "R39") (pin "2") (pinfunction "2_2") (pintype "passive"))
      (node (ref "R4") (pin "P$2") (pinfunction "S_P$2") (pintype "passive"))
    )
    (net (code "65") (name "unconnected-(OUTPUT-2-PadP2)") (class "Default")
      (node (ref "OUTPUT") (pin "P2") (pinfunction "2_P2") (pintype "passive"))
    )
    (net (code "66") (name "unconnected-(OUTPUT1-2-PadP2)") (class "Default")
      (node (ref "OUTPUT1") (pin "P2") (pinfunction "2_P2") (pintype "passive"))
    )
    (net (code "67") (name "unconnected-(OUTPUT2-2-PadP2)") (class "Default")
      (node (ref "OUTPUT2") (pin "P2") (pinfunction "2_P2") (pintype "passive"))
    )
    (net (code "68") (name "unconnected-(OUTPUT3-2-PadP2)") (class "Default")
      (node (ref "OUTPUT3") (pin "P2") (pinfunction "2_P2") (pintype "passive"))
    )
  )
)
